# main_slave.net
KiCad netlist of a schematic drawn in Altium Designer
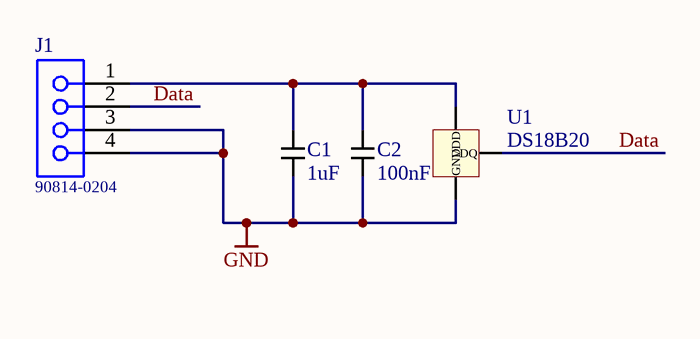
[diagram p0: main_slave.SchDoc]

(export (version "E")
  (design (tool "Eeschema 10.0.6"))
  (components
    (comp (ref "C1")
      (value "1uF")
      (footprint "C1206")
      (description "1uF, 1206")
      (libsource (lib "Capacitors") (part "1uF,1206"))
    )
    (comp (ref "C2")
      (value "100nF")
      (footprint "C1206")
      (description "100nF, 1206")
      (libsource (lib "Capacitors") (part "100nF,1206"))
    )
    (comp (ref "J1")
      (value "90814-0204")
      (footprint "MOLEX_90814-0204")
      (description "Pin Header, Signal, 1.27 mm, 1 Rows, 4 Contacts, Surface Mount Straight, Picoflex 90814 Series")
      (fields (field (name "MANUFACTURER") "MOLEX"))
      (libsource (lib "Connectoren") (part "90814-0204"))
    )
    (comp (ref "U1")
      (value "DS18B20")
      (footprint "TO-92_Twomes")
      (description "Temperature Sensor IC, Digital, ± 0.5°C, -55 °C, +125 °C")
      (libsource (lib "Misc") (part "DS18B20"))
    )
  )
  (nets
    (net (code "1") (name "/Data") (class "Default")
      (node (ref "J1") (pin "2") (pinfunction "2_2") (pintype "passive"))
      (node (ref "U1") (pin "2") (pinfunction "DQ_2") (pintype "bidirectional"))
    )
    (net (code "2") (name "GND") (class "Default")
      (node (ref "C1") (pin "1") (pinfunction "1_1") (pintype "passive"))
      (node (ref "C2") (pin "1") (pinfunction "1_1") (pintype "passive"))
      (node (ref "J1") (pin "3") (pinfunction "3_3") (pintype "passive"))
      (node (ref "J1") (pin "4") (pinfunction "4_4") (pintype "passive"))
      (node (ref "U1") (pin "1") (pinfunction "GND_1") (pintype "power_in"))
    )
    (net (code "3") (name "Net-(U1-VDD)") (class "Default")
      (node (ref "C1") (pin "2") (pinfunction "2_2") (pintype "passive"))
      (node (ref "C2") (pin "2") (pinfunction "2_2") (pintype "passive"))
      (node (ref "J1") (pin "1") (pinfunction "1_1") (pintype "passive"))
      (node (ref "U1") (pin "3") (pinfunction "VDD_3") (pintype "power_in"))
    )
  )
)
